# Sheet4.net
KiCad netlist of a schematic drawn in Altium Designer
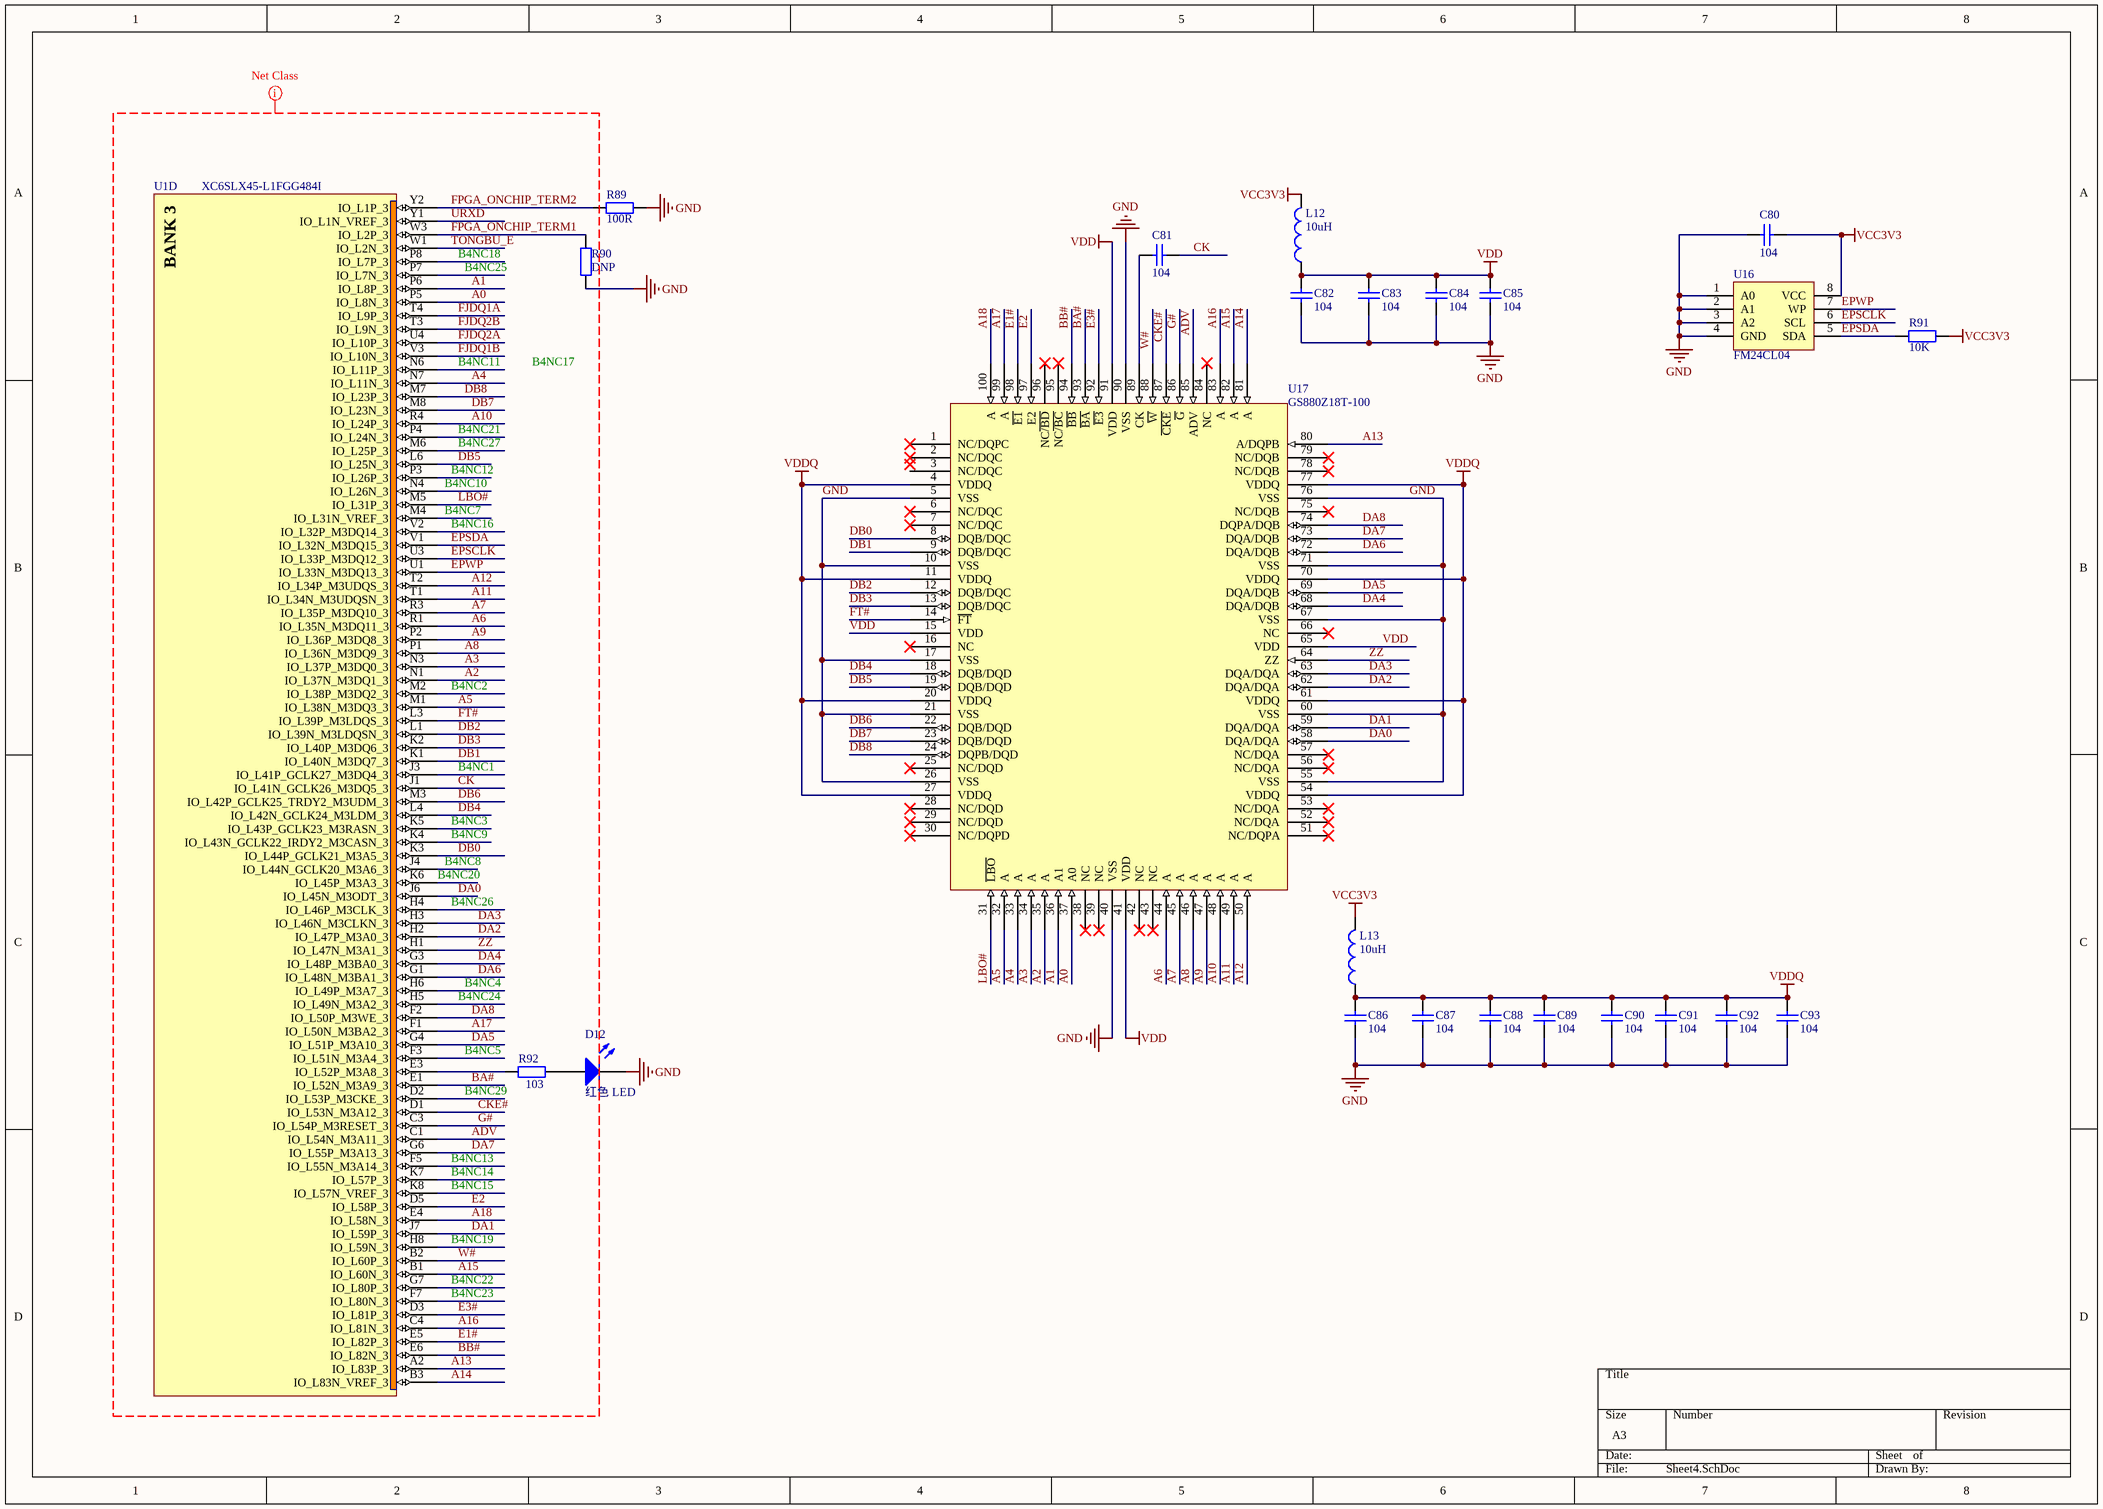
[diagram p0: Sheet4.SchDoc]

(export (version "E")
  (design (tool "Eeschema 10.0.6"))
  (components
    (comp (ref "C80")
      (value "104")
      (footprint "0402")
      (description "Capacitor")
      (fields (field (name "PUBLISHER") "Altium Limited"))
      (libsource (lib "Miscellaneous Devices") (part "Cap"))
    )
    (comp (ref "C81")
      (value "104")
      (footprint "0402")
      (description "Capacitor")
      (fields (field (name "PUBLISHER") "Altium Limited"))
      (libsource (lib "Miscellaneous Devices") (part "Cap"))
    )
    (comp (ref "C82")
      (value "104")
      (footprint "0402")
      (description "Capacitor")
      (fields (field (name "PUBLISHER") "Altium Limited"))
      (libsource (lib "Miscellaneous Devices") (part "Cap"))
    )
    (comp (ref "C83")
      (value "104")
      (footprint "0402")
      (description "Capacitor")
      (fields (field (name "PUBLISHER") "Altium Limited"))
      (libsource (lib "Miscellaneous Devices") (part "Cap"))
    )
    (comp (ref "C84")
      (value "104")
      (footprint "0402")
      (description "Capacitor")
      (fields (field (name "PUBLISHER") "Altium Limited"))
      (libsource (lib "Miscellaneous Devices") (part "Cap"))
    )
    (comp (ref "C85")
      (value "104")
      (footprint "0402")
      (description "Capacitor")
      (fields (field (name "PUBLISHER") "Altium Limited"))
      (libsource (lib "Miscellaneous Devices") (part "Cap"))
    )
    (comp (ref "C86")
      (value "104")
      (footprint "0402")
      (description "Capacitor")
      (fields (field (name "PUBLISHER") "Altium Limited"))
      (libsource (lib "Miscellaneous Devices") (part "Cap"))
    )
    (comp (ref "C87")
      (value "104")
      (footprint "0402")
      (description "Capacitor")
      (fields (field (name "PUBLISHER") "Altium Limited"))
      (libsource (lib "Miscellaneous Devices") (part "Cap"))
    )
    (comp (ref "C88")
      (value "104")
      (footprint "0402")
      (description "Capacitor")
      (fields (field (name "PUBLISHER") "Altium Limited"))
      (libsource (lib "Miscellaneous Devices") (part "Cap"))
    )
    (comp (ref "C89")
      (value "104")
      (footprint "0402")
      (description "Capacitor")
      (fields (field (name "PUBLISHER") "Altium Limited"))
      (libsource (lib "Miscellaneous Devices") (part "Cap"))
    )
    (comp (ref "C90")
      (value "104")
      (footprint "0402")
      (description "Capacitor")
      (fields (field (name "PUBLISHER") "Altium Limited"))
      (libsource (lib "Miscellaneous Devices") (part "Cap"))
    )
    (comp (ref "C91")
      (value "104")
      (footprint "0402")
      (description "Capacitor")
      (fields (field (name "PUBLISHER") "Altium Limited"))
      (libsource (lib "Miscellaneous Devices") (part "Cap"))
    )
    (comp (ref "C92")
      (value "104")
      (footprint "0402")
      (description "Capacitor")
      (fields (field (name "PUBLISHER") "Altium Limited"))
      (libsource (lib "Miscellaneous Devices") (part "Cap"))
    )
    (comp (ref "C93")
      (value "104")
      (footprint "0402")
      (description "Capacitor")
      (fields (field (name "PUBLISHER") "Altium Limited"))
      (libsource (lib "Miscellaneous Devices") (part "Cap"))
    )
    (comp (ref "D12")
      (value "红色 LED")
      (footprint "0805LED")
      (description "Typical INFRARED GaAs LED")
      (fields (field (name "PUBLISHER") "Altium Limited"))
      (libsource (lib "Miscellaneous Devices") (part "LED0"))
    )
    (comp (ref "L12")
      (value "10uH")
      (footprint "1206A")
      (description "Inductor")
      (fields (field (name "PUBLISHER") "Altium Limited"))
      (libsource (lib "Miscellaneous Devices") (part "Inductor"))
    )
    (comp (ref "L13")
      (value "10uH")
      (footprint "1206A")
      (description "Inductor")
      (fields (field (name "PUBLISHER") "Altium Limited"))
      (libsource (lib "Miscellaneous Devices") (part "Inductor"))
    )
    (comp (ref "R89")
      (value "100R")
      (footprint "0603")
      (description "Resistor")
      (fields (field (name "PUBLISHER") "Altium Limited"))
      (libsource (lib "Miscellaneous Devices") (part "Res2"))
    )
    (comp (ref "R90")
      (value "DNP")
      (footprint "0603")
      (description "Resistor")
      (fields (field (name "PUBLISHER") "Altium Limited"))
      (libsource (lib "") (part "Res2_1"))
    )
    (comp (ref "R91") (value "10K") (footprint "0603") (libsource (lib "Custom Schlib") (part "Resistor")))
    (comp (ref "R92")
      (value "103")
      (footprint "0603")
      (description "Resistor")
      (fields (field (name "PUBLISHER") "Altium Limited"))
      (libsource (lib "Miscellaneous Devices") (part "Res2"))
    )
    (comp (ref "U1")
      (value "XC6SLX45-L1FGG484I")
      (footprint "FGG484")
      (fields (field (name "PUBLISHER") "Altium Limited"))
      (libsource (lib "Xilinx Spartan-6") (part "XC6SLX45-L1FGG484I"))
    )
    (comp (ref "U16")
      (value "FM24CL04")
      (footprint "so_8")
      (libsource (lib "Custom Schlib") (part "FM24CL04"))
    )
    (comp (ref "U17")
      (value "GS880Z18T-100")
      (footprint "QFP65P1680X2280-100N")
      (libsource (lib "Mpd_Fpga_2") (part "GS880Z18BT100"))
    )
  )
  (nets
    (net (code "1") (name "/A0") (class "Default")
      (node (ref "U1") (pin "P5") (pinfunction "IO_L8N_3_P5") (pintype "bidirectional"))
      (node (ref "U17") (pin "37") (pinfunction "A0_37") (pintype "input"))
    )
    (net (code "2") (name "/A1") (class "Default")
      (node (ref "U1") (pin "P6") (pinfunction "IO_L8P_3_P6") (pintype "bidirectional"))
      (node (ref "U17") (pin "36") (pinfunction "A1_36") (pintype "input"))
    )
    (net (code "3") (name "/A2") (class "Default")
      (node (ref "U1") (pin "N1") (pinfunction "IO_L37N_M3DQ1_3_N1") (pintype "bidirectional"))
      (node (ref "U17") (pin "35") (pinfunction "A_35") (pintype "input"))
    )
    (net (code "4") (name "/A3") (class "Default")
      (node (ref "U1") (pin "N3") (pinfunction "IO_L37P_M3DQ0_3_N3") (pintype "bidirectional"))
      (node (ref "U17") (pin "34") (pinfunction "A_34") (pintype "input"))
    )
    (net (code "5") (name "/A4") (class "Default")
      (node (ref "U1") (pin "N7") (pinfunction "IO_L11N_3_N7") (pintype "bidirectional"))
      (node (ref "U17") (pin "33") (pinfunction "A_33") (pintype "input"))
    )
    (net (code "6") (name "/A5") (class "Default")
      (node (ref "U1") (pin "M1") (pinfunction "IO_L38N_M3DQ3_3_M1") (pintype "bidirectional"))
      (node (ref "U17") (pin "32") (pinfunction "A_32") (pintype "input"))
    )
    (net (code "7") (name "/A6") (class "Default")
      (node (ref "U1") (pin "R1") (pinfunction "IO_L35N_M3DQ11_3_R1") (pintype "bidirectional"))
      (node (ref "U17") (pin "44") (pinfunction "A_44") (pintype "input"))
    )
    (net (code "8") (name "/A7") (class "Default")
      (node (ref "U1") (pin "R3") (pinfunction "IO_L35P_M3DQ10_3_R3") (pintype "bidirectional"))
      (node (ref "U17") (pin "45") (pinfunction "A_45") (pintype "input"))
    )
    (net (code "9") (name "/A8") (class "Default")
      (node (ref "U1") (pin "P1") (pinfunction "IO_L36N_M3DQ9_3_P1") (pintype "bidirectional"))
      (node (ref "U17") (pin "46") (pinfunction "A_46") (pintype "input"))
    )
    (net (code "10") (name "/A9") (class "Default")
      (node (ref "U1") (pin "P2") (pinfunction "IO_L36P_M3DQ8_3_P2") (pintype "bidirectional"))
      (node (ref "U17") (pin "47") (pinfunction "A_47") (pintype "input"))
    )
    (net (code "11") (name "/A10") (class "Default")
      (node (ref "U1") (pin "R4") (pinfunction "IO_L24P_3_R4") (pintype "bidirectional"))
      (node (ref "U17") (pin "48") (pinfunction "A_48") (pintype "input"))
    )
    (net (code "12") (name "/A11") (class "Default")
      (node (ref "U1") (pin "T1") (pinfunction "IO_L34N_M3UDQSN_3_T1") (pintype "bidirectional"))
      (node (ref "U17") (pin "49") (pinfunction "A_49") (pintype "input"))
    )
    (net (code "13") (name "/A12") (class "Default")
      (node (ref "U1") (pin "T2") (pinfunction "IO_L34P_M3UDQS_3_T2") (pintype "bidirectional"))
      (node (ref "U17") (pin "50") (pinfunction "A_50") (pintype "input"))
    )
    (net (code "14") (name "/A13") (class "Default")
      (node (ref "U1") (pin "A2") (pinfunction "IO_L83P_3_A2") (pintype "bidirectional"))
      (node (ref "U17") (pin "80") (pinfunction "A/DQPB_80") (pintype "input"))
    )
    (net (code "15") (name "/A14") (class "Default")
      (node (ref "U1") (pin "B3") (pinfunction "IO_L83N_VREF_3_B3") (pintype "bidirectional"))
      (node (ref "U17") (pin "81") (pinfunction "A_81") (pintype "input"))
    )
    (net (code "16") (name "/A15") (class "Default")
      (node (ref "U1") (pin "B1") (pinfunction "IO_L60N_3_B1") (pintype "bidirectional"))
      (node (ref "U17") (pin "82") (pinfunction "A_82") (pintype "input"))
    )
    (net (code "17") (name "/A16") (class "Default")
      (node (ref "U1") (pin "C4") (pinfunction "IO_L81N_3_C4") (pintype "bidirectional"))
      (node (ref "U17") (pin "83") (pinfunction "A_83") (pintype "input"))
    )
    (net (code "18") (name "/A17") (class "Default")
      (node (ref "U1") (pin "F1") (pinfunction "IO_L50N_M3BA2_3_F1") (pintype "bidirectional"))
      (node (ref "U17") (pin "99") (pinfunction "A_99") (pintype "input"))
    )
    (net (code "19") (name "/A18") (class "Default")
      (node (ref "U1") (pin "E4") (pinfunction "IO_L58N_3_E4") (pintype "bidirectional"))
      (node (ref "U17") (pin "100") (pinfunction "A_100") (pintype "input"))
    )
    (net (code "20") (name "/ADV") (class "Default")
      (node (ref "U1") (pin "C1") (pinfunction "IO_L54N_M3A11_3_C1") (pintype "bidirectional"))
      (node (ref "U17") (pin "85") (pinfunction "ADV_85") (pintype "input"))
    )
    (net (code "21") (name "/B4NC1") (class "Default")
      (node (ref "U1") (pin "J3") (pinfunction "IO_L41P_GCLK27_M3DQ4_3_J3") (pintype "bidirectional"))
    )
    (net (code "22") (name "/B4NC2") (class "Default")
      (node (ref "U1") (pin "M2") (pinfunction "IO_L38P_M3DQ2_3_M2") (pintype "bidirectional"))
    )
    (net (code "23") (name "/B4NC3") (class "Default")
      (node (ref "U1") (pin "K5") (pinfunction "IO_L43P_GCLK23_M3RASN_3_K5") (pintype "bidirectional"))
    )
    (net (code "24") (name "/B4NC4") (class "Default")
      (node (ref "U1") (pin "H6") (pinfunction "IO_L49P_M3A7_3_H6") (pintype "bidirectional"))
    )
    (net (code "25") (name "/B4NC5") (class "Default")
      (node (ref "U1") (pin "F3") (pinfunction "IO_L51N_M3A4_3_F3") (pintype "bidirectional"))
    )
    (net (code "26") (name "/B4NC7") (class "Default")
      (node (ref "U1") (pin "M4") (pinfunction "IO_L31N_VREF_3_M4") (pintype "bidirectional"))
    )
    (net (code "27") (name "/B4NC8") (class "Default")
      (node (ref "U1") (pin "J4") (pinfunction "IO_L44N_GCLK20_M3A6_3_J4") (pintype "bidirectional"))
    )
    (net (code "28") (name "/B4NC9") (class "Default")
      (node (ref "U1") (pin "K4") (pinfunction "IO_L43N_GCLK22_IRDY2_M3CASN_3_K4") (pintype "bidirectional"))
    )
    (net (code "29") (name "/B4NC10") (class "Default")
      (node (ref "U1") (pin "N4") (pinfunction "IO_L26N_3_N4") (pintype "bidirectional"))
    )
    (net (code "30") (name "/B4NC11") (class "Default")
      (node (ref "U1") (pin "N6") (pinfunction "IO_L11P_3_N6") (pintype "bidirectional"))
    )
    (net (code "31") (name "/B4NC12") (class "Default")
      (node (ref "U1") (pin "P3") (pinfunction "IO_L26P_3_P3") (pintype "bidirectional"))
    )
    (net (code "32") (name "/B4NC13") (class "Default")
      (node (ref "U1") (pin "F5") (pinfunction "IO_L55N_M3A14_3_F5") (pintype "bidirectional"))
    )
    (net (code "33") (name "/B4NC14") (class "Default")
      (node (ref "U1") (pin "K7") (pinfunction "IO_L57P_3_K7") (pintype "bidirectional"))
    )
    (net (code "34") (name "/B4NC15") (class "Default")
      (node (ref "U1") (pin "K8") (pinfunction "IO_L57N_VREF_3_K8") (pintype "bidirectional"))
    )
    (net (code "35") (name "/B4NC16") (class "Default")
      (node (ref "U1") (pin "V2") (pinfunction "IO_L32P_M3DQ14_3_V2") (pintype "bidirectional"))
    )
    (net (code "37") (name "/B4NC18") (class "Default")
      (node (ref "U1") (pin "P8") (pinfunction "IO_L7P_3_P8") (pintype "bidirectional"))
    )
    (net (code "38") (name "/B4NC19") (class "Default")
      (node (ref "U1") (pin "H8") (pinfunction "IO_L59N_3_H8") (pintype "bidirectional"))
    )
    (net (code "39") (name "/B4NC20") (class "Default")
      (node (ref "U1") (pin "K6") (pinfunction "IO_L45P_M3A3_3_K6") (pintype "bidirectional"))
    )
    (net (code "40") (name "/B4NC21") (class "Default")
      (node (ref "U1") (pin "P4") (pinfunction "IO_L24N_3_P4") (pintype "bidirectional"))
    )
    (net (code "41") (name "/B4NC22") (class "Default")
      (node (ref "U1") (pin "G7") (pinfunction "IO_L80P_3_G7") (pintype "bidirectional"))
    )
    (net (code "42") (name "/B4NC23") (class "Default")
      (node (ref "U1") (pin "F7") (pinfunction "IO_L80N_3_F7") (pintype "bidirectional"))
    )
    (net (code "43") (name "/B4NC24") (class "Default")
      (node (ref "U1") (pin "H5") (pinfunction "IO_L49N_M3A2_3_H5") (pintype "bidirectional"))
    )
    (net (code "44") (name "/B4NC25") (class "Default")
      (node (ref "U1") (pin "P7") (pinfunction "IO_L7N_3_P7") (pintype "bidirectional"))
    )
    (net (code "45") (name "/B4NC26") (class "Default")
      (node (ref "U1") (pin "H4") (pinfunction "IO_L46P_M3CLK_3_H4") (pintype "bidirectional"))
    )
    (net (code "46") (name "/B4NC27") (class "Default")
      (node (ref "U1") (pin "M6") (pinfunction "IO_L25P_3_M6") (pintype "bidirectional"))
    )
    (net (code "47") (name "/B4NC29") (class "Default")
      (node (ref "U1") (pin "D2") (pinfunction "IO_L53P_M3CKE_3_D2") (pintype "bidirectional"))
    )
    (net (code "48") (name "/BA#") (class "Default")
      (node (ref "U1") (pin "E1") (pinfunction "IO_L52N_M3A9_3_E1") (pintype "bidirectional"))
      (node (ref "U17") (pin "93") (pinfunction "~{BA}_93") (pintype "input"))
    )
    (net (code "49") (name "/BB#") (class "Default")
      (node (ref "U1") (pin "E6") (pinfunction "IO_L82N_3_E6") (pintype "bidirectional"))
      (node (ref "U17") (pin "94") (pinfunction "~{BB}_94") (pintype "input"))
    )
    (net (code "50") (name "/CK") (class "Default")
      (node (ref "C81") (pin "1") (pinfunction "1_1") (pintype "passive"))
      (node (ref "U1") (pin "J1") (pinfunction "IO_L41N_GCLK26_M3DQ5_3_J1") (pintype "bidirectional"))
    )
    (net (code "51") (name "/CKE#") (class "Default")
      (node (ref "U1") (pin "D1") (pinfunction "IO_L53N_M3A12_3_D1") (pintype "bidirectional"))
      (node (ref "U17") (pin "87") (pinfunction "~{CKE}_87") (pintype "input"))
    )
    (net (code "52") (name "/DA0") (class "Default")
      (node (ref "U1") (pin "J6") (pinfunction "IO_L45N_M3ODT_3_J6") (pintype "bidirectional"))
      (node (ref "U17") (pin "58") (pinfunction "DQA/DQA_58") (pintype "bidirectional"))
    )
    (net (code "53") (name "/DA1") (class "Default")
      (node (ref "U1") (pin "J7") (pinfunction "IO_L59P_3_J7") (pintype "bidirectional"))
      (node (ref "U17") (pin "59") (pinfunction "DQA/DQA_59") (pintype "bidirectional"))
    )
    (net (code "54") (name "/DA2") (class "Default")
      (node (ref "U1") (pin "H2") (pinfunction "IO_L47P_M3A0_3_H2") (pintype "bidirectional"))
      (node (ref "U17") (pin "62") (pinfunction "DQA/DQA_62") (pintype "bidirectional"))
    )
    (net (code "55") (name "/DA3") (class "Default")
      (node (ref "U1") (pin "H3") (pinfunction "IO_L46N_M3CLKN_3_H3") (pintype "bidirectional"))
      (node (ref "U17") (pin "63") (pinfunction "DQA/DQA_63") (pintype "bidirectional"))
    )
    (net (code "56") (name "/DA4") (class "Default")
      (node (ref "U1") (pin "G3") (pinfunction "IO_L48P_M3BA0_3_G3") (pintype "bidirectional"))
      (node (ref "U17") (pin "68") (pinfunction "DQA/DQB_68") (pintype "bidirectional"))
    )
    (net (code "57") (name "/DA5") (class "Default")
      (node (ref "U1") (pin "G4") (pinfunction "IO_L51P_M3A10_3_G4") (pintype "bidirectional"))
      (node (ref "U17") (pin "69") (pinfunction "DQA/DQB_69") (pintype "bidirectional"))
    )
    (net (code "58") (name "/DA6") (class "Default")
      (node (ref "U1") (pin "G1") (pinfunction "IO_L48N_M3BA1_3_G1") (pintype "bidirectional"))
      (node (ref "U17") (pin "72") (pinfunction "DQA/DQB_72") (pintype "bidirectional"))
    )
    (net (code "59") (name "/DA7") (class "Default")
      (node (ref "U1") (pin "G6") (pinfunction "IO_L55P_M3A13_3_G6") (pintype "bidirectional"))
      (node (ref "U17") (pin "73") (pinfunction "DQA/DQB_73") (pintype "bidirectional"))
    )
    (net (code "60") (name "/DA8") (class "Default")
      (node (ref "U1") (pin "F2") (pinfunction "IO_L50P_M3WE_3_F2") (pintype "bidirectional"))
      (node (ref "U17") (pin "74") (pinfunction "DQPA/DQB_74") (pintype "bidirectional"))
    )
    (net (code "61") (name "/DB0") (class "Default")
      (node (ref "U1") (pin "K3") (pinfunction "IO_L44P_GCLK21_M3A5_3_K3") (pintype "bidirectional"))
      (node (ref "U17") (pin "8") (pinfunction "DQB/DQC_8") (pintype "bidirectional"))
    )
    (net (code "62") (name "/DB1") (class "Default")
      (node (ref "U1") (pin "K1") (pinfunction "IO_L40N_M3DQ7_3_K1") (pintype "bidirectional"))
      (node (ref "U17") (pin "9") (pinfunction "DQB/DQC_9") (pintype "bidirectional"))
    )
    (net (code "63") (name "/DB2") (class "Default")
      (node (ref "U1") (pin "L1") (pinfunction "IO_L39N_M3LDQSN_3_L1") (pintype "bidirectional"))
      (node (ref "U17") (pin "12") (pinfunction "DQB/DQC_12") (pintype "bidirectional"))
    )
    (net (code "64") (name "/DB3") (class "Default")
      (node (ref "U1") (pin "K2") (pinfunction "IO_L40P_M3DQ6_3_K2") (pintype "bidirectional"))
      (node (ref "U17") (pin "13") (pinfunction "DQB/DQC_13") (pintype "bidirectional"))
    )
    (net (code "65") (name "/DB4") (class "Default")
      (node (ref "U1") (pin "L4") (pinfunction "IO_L42N_GCLK24_M3LDM_3_L4") (pintype "bidirectional"))
      (node (ref "U17") (pin "18") (pinfunction "DQB/DQD_18") (pintype "bidirectional"))
    )
    (net (code "66") (name "/DB5") (class "Default")
      (node (ref "U1") (pin "L6") (pinfunction "IO_L25N_3_L6") (pintype "bidirectional"))
      (node (ref "U17") (pin "19") (pinfunction "DQB/DQD_19") (pintype "bidirectional"))
    )
    (net (code "67") (name "/DB6") (class "Default")
      (node (ref "U1") (pin "M3") (pinfunction "IO_L42P_GCLK25_TRDY2_M3UDM_3_M3") (pintype "bidirectional"))
      (node (ref "U17") (pin "22") (pinfunction "DQB/DQD_22") (pintype "bidirectional"))
    )
    (net (code "68") (name "/DB7") (class "Default")
      (node (ref "U1") (pin "M8") (pinfunction "IO_L23N_3_M8") (pintype "bidirectional"))
      (node (ref "U17") (pin "23") (pinfunction "DQB/DQD_23") (pintype "bidirectional"))
    )
    (net (code "69") (name "/DB8") (class "Default")
      (node (ref "U1") (pin "M7") (pinfunction "IO_L23P_3_M7") (pintype "bidirectional"))
      (node (ref "U17") (pin "24") (pinfunction "DQPB/DQD_24") (pintype "bidirectional"))
    )
    (net (code "70") (name "/E1#") (class "Default")
      (node (ref "U1") (pin "E5") (pinfunction "IO_L82P_3_E5") (pintype "bidirectional"))
      (node (ref "U17") (pin "98") (pinfunction "~{E1}_98") (pintype "input"))
    )
    (net (code "71") (name "/E2") (class "Default")
      (node (ref "U1") (pin "D5") (pinfunction "IO_L58P_3_D5") (pintype "bidirectional"))
      (node (ref "U17") (pin "97") (pinfunction "E2_97") (pintype "input"))
    )
    (net (code "72") (name "/E3#") (class "Default")
      (node (ref "U1") (pin "D3") (pinfunction "IO_L81P_3_D3") (pintype "bidirectional"))
      (node (ref "U17") (pin "92") (pinfunction "~{E3}_92") (pintype "input"))
    )
    (net (code "73") (name "/EPSCLK") (class "Default")
      (node (ref "U1") (pin "U3") (pinfunction "IO_L33P_M3DQ12_3_U3") (pintype "bidirectional"))
      (node (ref "U16") (pin "6") (pinfunction "SCL_6") (pintype "passive"))
    )
    (net (code "74") (name "/EPSDA") (class "Default")
      (node (ref "R91") (pin "1") (pinfunction "1_1") (pintype "passive"))
      (node (ref "U1") (pin "V1") (pinfunction "IO_L32N_M3DQ15_3_V1") (pintype "bidirectional"))
      (node (ref "U16") (pin "5") (pinfunction "SDA_5") (pintype "passive"))
    )
    (net (code "75") (name "/EPWP") (class "Default")
      (node (ref "U1") (pin "U1") (pinfunction "IO_L33N_M3DQ13_3_U1") (pintype "bidirectional"))
      (node (ref "U16") (pin "7") (pinfunction "WP_7") (pintype "passive"))
    )
    (net (code "76") (name "/FJDQ1A") (class "Default")
      (node (ref "U1") (pin "T4") (pinfunction "IO_L9P_3_T4") (pintype "bidirectional"))
    )
    (net (code "77") (name "/FJDQ1B") (class "Default")
      (node (ref "U1") (pin "V3") (pinfunction "IO_L10N_3_V3") (pintype "bidirectional"))
    )
    (net (code "78") (name "/FJDQ2A") (class "Default")
      (node (ref "U1") (pin "U4") (pinfunction "IO_L10P_3_U4") (pintype "bidirectional"))
    )
    (net (code "79") (name "/FJDQ2B") (class "Default")
      (node (ref "U1") (pin "T3") (pinfunction "IO_L9N_3_T3") (pintype "bidirectional"))
    )
    (net (code "80") (name "/FPGA_ONCHIP_TERM1") (class "Default")
      (node (ref "R90") (pin "1") (pinfunction "1_1") (pintype "passive"))
      (node (ref "U1") (pin "W3") (pinfunction "IO_L2P_3_W3") (pintype "bidirectional"))
    )
    (net (code "81") (name "/FPGA_ONCHIP_TERM2") (class "Default")
      (node (ref "R89") (pin "1") (pinfunction "1_1") (pintype "passive"))
      (node (ref "U1") (pin "Y2") (pinfunction "IO_L1P_3_Y2") (pintype "bidirectional"))
    )
    (net (code "82") (name "/FT#") (class "Default")
      (node (ref "U1") (pin "L3") (pinfunction "IO_L39P_M3LDQS_3_L3") (pintype "bidirectional"))
      (node (ref "U17") (pin "14") (pinfunction "~{FT}_14") (pintype "input"))
    )
    (net (code "83") (name "/G#") (class "Default")
      (node (ref "U1") (pin "C3") (pinfunction "IO_L54P_M3RESET_3_C3") (pintype "bidirectional"))
      (node (ref "U17") (pin "86") (pinfunction "~{G}_86") (pintype "input"))
    )
    (net (code "84") (name "/LBO#") (class "Default")
      (node (ref "U1") (pin "M5") (pinfunction "IO_L31P_3_M5") (pintype "bidirectional"))
      (node (ref "U17") (pin "31") (pinfunction "~{LBO}_31") (pintype "input"))
    )
    (net (code "85") (name "/TONGBU_E") (class "Default")
      (node (ref "U1") (pin "W1") (pinfunction "IO_L2N_3_W1") (pintype "bidirectional"))
    )
    (net (code "86") (name "/URXD") (class "Default")
      (node (ref "U1") (pin "Y1") (pinfunction "IO_L1N_VREF_3_Y1") (pintype "bidirectional"))
    )
    (net (code "87") (name "/W#") (class "Default")
      (node (ref "U1") (pin "B2") (pinfunction "IO_L60P_3_B2") (pintype "bidirectional"))
      (node (ref "U17") (pin "88") (pinfunction "~{W}_88") (pintype "input"))
    )
    (net (code "88") (name "/ZZ") (class "Default")
      (node (ref "U1") (pin "H1") (pinfunction "IO_L47N_M3A1_3_H1") (pintype "bidirectional"))
      (node (ref "U17") (pin "64") (pinfunction "ZZ_64") (pintype "input"))
    )
    (net (code "89") (name "GND") (class "Default")
      (node (ref "C80") (pin "2") (pinfunction "2_2") (pintype "passive"))
      (node (ref "C82") (pin "1") (pinfunction "1_1") (pintype "passive"))
      (node (ref "C83") (pin "1") (pinfunction "1_1") (pintype "passive"))
      (node (ref "C84") (pin "1") (pinfunction "1_1") (pintype "passive"))
      (node (ref "C85") (pin "1") (pinfunction "1_1") (pintype "passive"))
      (node (ref "C86") (pin "1") (pinfunction "1_1") (pintype "passive"))
      (node (ref "C87") (pin "1") (pinfunction "1_1") (pintype "passive"))
      (node (ref "C88") (pin "1") (pinfunction "1_1") (pintype "passive"))
      (node (ref "C89") (pin "1") (pinfunction "1_1") (pintype "passive"))
      (node (ref "C90") (pin "1") (pinfunction "1_1") (pintype "passive"))
      (node (ref "C91") (pin "1") (pinfunction "1_1") (pintype "passive"))
      (node (ref "C92") (pin "1") (pinfunction "1_1") (pintype "passive"))
      (node (ref "C93") (pin "1") (pinfunction "1_1") (pintype "passive"))
      (node (ref "D12") (pin "2") (pinfunction "K_2") (pintype "passive"))
      (node (ref "R89") (pin "2") (pinfunction "2_2") (pintype "passive"))
      (node (ref "R90") (pin "2") (pinfunction "2_2") (pintype "passive"))
      (node (ref "U16") (pin "1") (pinfunction "A0_1") (pintype "passive"))
      (node (ref "U16") (pin "2") (pinfunction "A1_2") (pintype "passive"))
      (node (ref "U16") (pin "3") (pinfunction "A2_3") (pintype "passive"))
      (node (ref "U16") (pin "4") (pinfunction "GND_4") (pintype "passive"))
      (node (ref "U17") (pin "10") (pinfunction "VSS_10") (pintype "power_in"))
      (node (ref "U17") (pin "17") (pinfunction "VSS_17") (pintype "power_in"))
      (node (ref "U17") (pin "21") (pinfunction "VSS_21") (pintype "power_in"))
      (node (ref "U17") (pin "26") (pinfunction "VSS_26") (pintype "power_in"))
      (node (ref "U17") (pin "40") (pinfunction "VSS_40") (pintype "power_in"))
      (node (ref "U17") (pin "5") (pinfunction "VSS_5") (pintype "power_in"))
      (node (ref "U17") (pin "55") (pinfunction "VSS_55") (pintype "power_in"))
      (node (ref "U17") (pin "60") (pinfunction "VSS_60") (pintype "power_in"))
      (node (ref "U17") (pin "67") (pinfunction "VSS_67") (pintype "power_in"))
      (node (ref "U17") (pin "71") (pinfunction "VSS_71") (pintype "power_in"))
      (node (ref "U17") (pin "76") (pinfunction "VSS_76") (pintype "power_in"))
      (node (ref "U17") (pin "90") (pinfunction "VSS_90") (pintype "power_in"))
    )
    (net (code "90") (name "Net-(D12-A)") (class "Default")
      (node (ref "D12") (pin "1") (pinfunction "A_1") (pintype "passive"))
      (node (ref "R92") (pin "2") (pinfunction "2_2") (pintype "passive"))
    )
    (net (code "91") (name "Net-(U1D-IO_L52P_M3A8_3)") (class "Default")
      (node (ref "R92") (pin "1") (pinfunction "1_1") (pintype "passive"))
      (node (ref "U1") (pin "E3") (pinfunction "IO_L52P_M3A8_3_E3") (pintype "bidirectional"))
    )
    (net (code "92") (name "Net-(U17-CK)") (class "Default")
      (node (ref "C81") (pin "2") (pinfunction "2_2") (pintype "passive"))
      (node (ref "U17") (pin "89") (pinfunction "CK_89") (pintype "input"))
    )
    (net (code "93") (name "VCC3V3") (class "Default")
      (node (ref "C80") (pin "1") (pinfunction "1_1") (pintype "passive"))
      (node (ref "L12") (pin "2") (pinfunction "2_2") (pintype "passive"))
      (node (ref "L13") (pin "2") (pinfunction "2_2") (pintype "passive"))
      (node (ref "R91") (pin "2") (pinfunction "2_2") (pintype "passive"))
      (node (ref "U16") (pin "8") (pinfunction "VCC_8") (pintype "passive"))
    )
    (net (code "94") (name "VDD") (class "Default")
      (node (ref "C82") (pin "2") (pinfunction "2_2") (pintype "passive"))
      (node (ref "C83") (pin "2") (pinfunction "2_2") (pintype "passive"))
      (node (ref "C84") (pin "2") (pinfunction "2_2") (pintype "passive"))
      (node (ref "C85") (pin "2") (pinfunction "2_2") (pintype "passive"))
      (node (ref "L12") (pin "1") (pinfunction "1_1") (pintype "passive"))
      (node (ref "U17") (pin "15") (pinfunction "VDD_15") (pintype "power_in"))
      (node (ref "U17") (pin "41") (pinfunction "VDD_41") (pintype "power_in"))
      (node (ref "U17") (pin "65") (pinfunction "VDD_65") (pintype "power_in"))
      (node (ref "U17") (pin "91") (pinfunction "VDD_91") (pintype "power_in"))
    )
    (net (code "95") (name "VDDQ") (class "Default")
      (node (ref "C86") (pin "2") (pinfunction "2_2") (pintype "passive"))
      (node (ref "C87") (pin "2") (pinfunction "2_2") (pintype "passive"))
      (node (ref "C88") (pin "2") (pinfunction "2_2") (pintype "passive"))
      (node (ref "C89") (pin "2") (pinfunction "2_2") (pintype "passive"))
      (node (ref "C90") (pin "2") (pinfunction "2_2") (pintype "passive"))
      (node (ref "C91") (pin "2") (pinfunction "2_2") (pintype "passive"))
      (node (ref "C92") (pin "2") (pinfunction "2_2") (pintype "passive"))
      (node (ref "C93") (pin "2") (pinfunction "2_2") (pintype "passive"))
      (node (ref "L13") (pin "1") (pinfunction "1_1") (pintype "passive"))
      (node (ref "U17") (pin "11") (pinfunction "VDDQ_11") (pintype "power_in"))
      (node (ref "U17") (pin "20") (pinfunction "VDDQ_20") (pintype "power_in"))
      (node (ref "U17") (pin "27") (pinfunction "VDDQ_27") (pintype "power_in"))
      (node (ref "U17") (pin "4") (pinfunction "VDDQ_4") (pintype "power_in"))
      (node (ref "U17") (pin "54") (pinfunction "VDDQ_54") (pintype "power_in"))
      (node (ref "U17") (pin "61") (pinfunction "VDDQ_61") (pintype "power_in"))
      (node (ref "U17") (pin "70") (pinfunction "VDDQ_70") (pintype "power_in"))
      (node (ref "U17") (pin "77") (pinfunction "VDDQ_77") (pintype "power_in"))
    )
    (net (code "96") (name "unconnected-(U17-NC-Pad16)") (class "Default")
      (node (ref "U17") (pin "16") (pinfunction "NC_16") (pintype "passive+no_connect"))
    )
    (net (code "97") (name "unconnected-(U17-NC-Pad38)") (class "Default")
      (node (ref "U17") (pin "38") (pinfunction "NC_38") (pintype "passive+no_connect"))
    )
    (net (code "98") (name "unconnected-(U17-NC-Pad39)") (class "Default")
      (node (ref "U17") (pin "39") (pinfunction "NC_39") (pintype "passive+no_connect"))
    )
    (net (code "99") (name "unconnected-(U17-NC-Pad42)") (class "Default")
      (node (ref "U17") (pin "42") (pinfunction "NC_42") (pintype "passive+no_connect"))
    )
    (net (code "100") (name "unconnected-(U17-NC-Pad43)") (class "Default")
      (node (ref "U17") (pin "43") (pinfunction "NC_43") (pintype "passive+no_connect"))
    )
    (net (code "101") (name "unconnected-(U17-NC-Pad66)") (class "Default")
      (node (ref "U17") (pin "66") (pinfunction "NC_66") (pintype "passive+no_connect"))
    )
    (net (code "102") (name "unconnected-(U17-NC-Pad84)") (class "Default")
      (node (ref "U17") (pin "84") (pinfunction "NC_84") (pintype "passive+no_connect"))
    )
    (net (code "103") (name "unconnected-(U17-NC{slash}DQA-Pad52)") (class "Default")
      (node (ref "U17") (pin "52") (pinfunction "NC/DQA_52") (pintype "passive+no_connect"))
    )
    (net (code "104") (name "unconnected-(U17-NC{slash}DQA-Pad53)") (class "Default")
      (node (ref "U17") (pin "53") (pinfunction "NC/DQA_53") (pintype "passive+no_connect"))
    )
    (net (code "105") (name "unconnected-(U17-NC{slash}DQA-Pad56)") (class "Default")
      (node (ref "U17") (pin "56") (pinfunction "NC/DQA_56") (pintype "passive+no_connect"))
    )
    (net (code "106") (name "unconnected-(U17-NC{slash}DQA-Pad57)") (class "Default")
      (node (ref "U17") (pin "57") (pinfunction "NC/DQA_57") (pintype "passive+no_connect"))
    )
    (net (code "107") (name "unconnected-(U17-NC{slash}DQB-Pad75)") (class "Default")
      (node (ref "U17") (pin "75") (pinfunction "NC/DQB_75") (pintype "passive+no_connect"))
    )
    (net (code "108") (name "unconnected-(U17-NC{slash}DQB-Pad78)") (class "Default")
      (node (ref "U17") (pin "78") (pinfunction "NC/DQB_78") (pintype "passive+no_connect"))
    )
    (net (code "109") (name "unconnected-(U17-NC{slash}DQB-Pad79)") (class "Default")
      (node (ref "U17") (pin "79") (pinfunction "NC/DQB_79") (pintype "passive+no_connect"))
    )
    (net (code "110") (name "unconnected-(U17-NC{slash}DQC-Pad2)") (class "Default")
      (node (ref "U17") (pin "2") (pinfunction "NC/DQC_2") (pintype "passive+no_connect"))
    )
    (net (code "111") (name "unconnected-(U17-NC{slash}DQC-Pad3)") (class "Default")
      (node (ref "U17") (pin "3") (pinfunction "NC/DQC_3") (pintype "passive"))
    )
    (net (code "112") (name "unconnected-(U17-NC{slash}DQC-Pad6)") (class "Default")
      (node (ref "U17") (pin "6") (pinfunction "NC/DQC_6") (pintype "passive+no_connect"))
    )
    (net (code "113") (name "unconnected-(U17-NC{slash}DQC-Pad7)") (class "Default")
      (node (ref "U17") (pin "7") (pinfunction "NC/DQC_7") (pintype "passive+no_connect"))
    )
    (net (code "114") (name "unconnected-(U17-NC{slash}DQD-Pad25)") (class "Default")
      (node (ref "U17") (pin "25") (pinfunction "NC/DQD_25") (pintype "passive+no_connect"))
    )
    (net (code "115") (name "unconnected-(U17-NC{slash}DQD-Pad28)") (class "Default")
      (node (ref "U17") (pin "28") (pinfunction "NC/DQD_28") (pintype "passive+no_connect"))
    )
    (net (code "116") (name "unconnected-(U17-NC{slash}DQD-Pad29)") (class "Default")
      (node (ref "U17") (pin "29") (pinfunction "NC/DQD_29") (pintype "passive+no_connect"))
    )
    (net (code "117") (name "unconnected-(U17-NC{slash}DQPA-Pad51)") (class "Default")
      (node (ref "U17") (pin "51") (pinfunction "NC/DQPA_51") (pintype "passive+no_connect"))
    )
    (net (code "118") (name "unconnected-(U17-NC{slash}DQPC-Pad1)") (class "Default")
      (node (ref "U17") (pin "1") (pinfunction "NC/DQPC_1") (pintype "passive+no_connect"))
    )
    (net (code "119") (name "unconnected-(U17-NC{slash}DQPD-Pad30)") (class "Default")
      (node (ref "U17") (pin "30") (pinfunction "NC/DQPD_30") (pintype "passive+no_connect"))
    )
    (net (code "120") (name "unconnected-(U17-NC~{{slash}BC}-Pad95)") (class "Default")
      (node (ref "U17") (pin "95") (pinfunction "NC~{/BC}_95") (pintype "passive+no_connect"))
    )
    (net (code "121") (name "unconnected-(U17-NC~{{slash}BD}-Pad96)") (class "Default")
      (node (ref "U17") (pin "96") (pinfunction "NC~{/BD}_96") (pintype "passive+no_connect"))
    )
  )
)
